# encoder.net
KiCad netlist of a schematic drawn in EAGLE
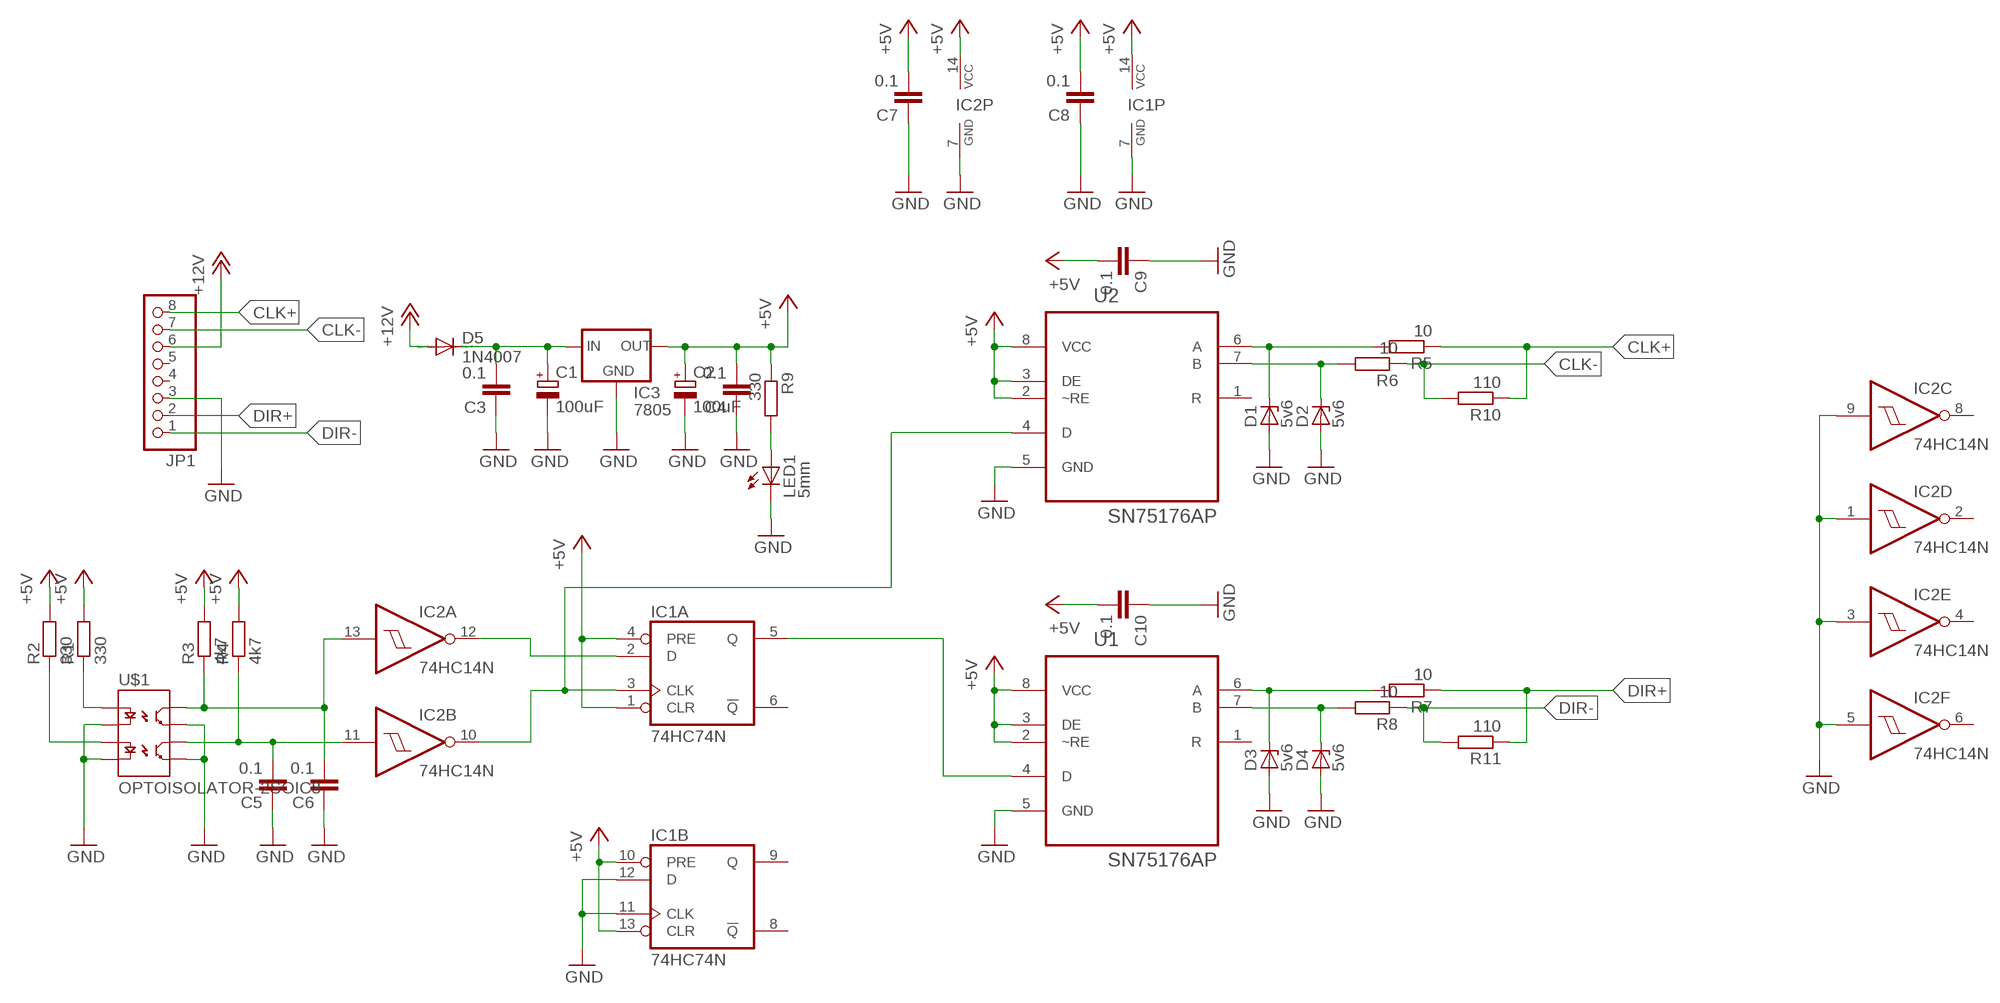
[diagram p0: schematic, sheet 1]

(export (version "E")
  (design (tool "Eeschema 10.0.6"))
  (components
    (comp (ref "C1")
      (value "100uF")
      (footprint "eagle-import:E3,5-8")
      (libsource (lib "eagle-import") (part "CPOL-EUE3.5-8"))
    )
    (comp (ref "C2")
      (value "100uF")
      (footprint "eagle-import:E3,5-8")
      (libsource (lib "eagle-import") (part "CPOL-EUE3.5-8"))
    )
    (comp (ref "C3")
      (value "0.1")
      (footprint "eagle-import:C050-025X075")
      (libsource (lib "eagle-import") (part "C-EU050-025X075"))
    )
    (comp (ref "C4")
      (value "0.1")
      (footprint "eagle-import:C050-025X075")
      (libsource (lib "eagle-import") (part "C-EU050-025X075"))
    )
    (comp (ref "C5")
      (value "0.1")
      (footprint "eagle-import:C050-025X075")
      (libsource (lib "eagle-import") (part "C-EU050-025X075"))
    )
    (comp (ref "C6")
      (value "0.1")
      (footprint "eagle-import:C050-025X075")
      (libsource (lib "eagle-import") (part "C-EU050-025X075"))
    )
    (comp (ref "C7")
      (value "0.1")
      (footprint "eagle-import:C050-025X075")
      (libsource (lib "eagle-import") (part "C-EU050-025X075"))
    )
    (comp (ref "C8")
      (value "0.1")
      (footprint "eagle-import:C050-025X075")
      (libsource (lib "eagle-import") (part "C-EU050-025X075"))
    )
    (comp (ref "C9")
      (value "0.1")
      (footprint "eagle-import:C050-025X075")
      (libsource (lib "eagle-import") (part "C-EU050-025X075"))
    )
    (comp (ref "C10")
      (value "0.1")
      (footprint "eagle-import:C050-025X075")
      (libsource (lib "eagle-import") (part "C-EU050-025X075"))
    )
    (comp (ref "D1")
      (value "5v6")
      (footprint "eagle-import:ZDIO-7.5")
      (libsource (lib "eagle-import") (part "ZENER-DIODEZD-7.5"))
    )
    (comp (ref "D2")
      (value "5v6")
      (footprint "eagle-import:ZDIO-7.5")
      (libsource (lib "eagle-import") (part "ZENER-DIODEZD-7.5"))
    )
    (comp (ref "D3")
      (value "5v6")
      (footprint "eagle-import:ZDIO-7.5")
      (libsource (lib "eagle-import") (part "ZENER-DIODEZD-7.5"))
    )
    (comp (ref "D4")
      (value "5v6")
      (footprint "eagle-import:ZDIO-7.5")
      (libsource (lib "eagle-import") (part "ZENER-DIODEZD-7.5"))
    )
    (comp (ref "D5")
      (value "1N4007")
      (footprint "eagle-import:DO41-7.6")
      (libsource (lib "eagle-import") (part "DIODE-DO41-7.6"))
    )
    (comp (ref "IC1")
      (value "74HC74N")
      (footprint "eagle-import:DIL14")
      (libsource (lib "eagle-import") (part "7474NAC"))
    )
    (comp (ref "IC2")
      (value "74HC14N")
      (footprint "eagle-import:DIL14")
      (libsource (lib "eagle-import") (part "7414NAC"))
    )
    (comp (ref "IC3")
      (value "7805")
      (footprint "eagle-import:78XXS")
      (libsource (lib "eagle-import") (part "78XXS"))
    )
    (comp (ref "JP1")
      (value "PINHD-1X8")
      (footprint "eagle-import:1X08")
      (libsource (lib "eagle-import") (part "PINHD-1X8"))
    )
    (comp (ref "LED1")
      (value "5mm")
      (footprint "eagle-import:LED5MM")
      (libsource (lib "eagle-import") (part "LED5MM"))
    )
    (comp (ref "R1")
      (value "330")
      (footprint "eagle-import:0204_7")
      (libsource (lib "eagle-import") (part "R-EU_0204/7"))
    )
    (comp (ref "R2")
      (value "330")
      (footprint "eagle-import:0204_7")
      (libsource (lib "eagle-import") (part "R-EU_0204/7"))
    )
    (comp (ref "R3")
      (value "4k7")
      (footprint "eagle-import:0204_7")
      (libsource (lib "eagle-import") (part "R-EU_0204/7"))
    )
    (comp (ref "R4")
      (value "4k7")
      (footprint "eagle-import:0204_7")
      (libsource (lib "eagle-import") (part "R-EU_0204/7"))
    )
    (comp (ref "R5")
      (value "10")
      (footprint "eagle-import:0204_7")
      (libsource (lib "eagle-import") (part "R-EU_0204/7"))
    )
    (comp (ref "R6")
      (value "10")
      (footprint "eagle-import:0204_7")
      (libsource (lib "eagle-import") (part "R-EU_0204/7"))
    )
    (comp (ref "R7")
      (value "10")
      (footprint "eagle-import:0204_7")
      (libsource (lib "eagle-import") (part "R-EU_0204/7"))
    )
    (comp (ref "R8")
      (value "10")
      (footprint "eagle-import:0204_7")
      (libsource (lib "eagle-import") (part "R-EU_0204/7"))
    )
    (comp (ref "R9")
      (value "330")
      (footprint "eagle-import:0204_7")
      (libsource (lib "eagle-import") (part "R-EU_0204/7"))
    )
    (comp (ref "R10")
      (value "110")
      (footprint "eagle-import:0204_7")
      (libsource (lib "eagle-import") (part "R-EU_0204/7"))
    )
    (comp (ref "R11")
      (value "110")
      (footprint "eagle-import:0204_7")
      (libsource (lib "eagle-import") (part "R-EU_0204/7"))
    )
    (comp (ref "U$1")
      (value "OPTOISOLATOR-2SOIC8")
      (footprint "eagle-import:SO08-2")
      (libsource (lib "eagle-import") (part "OPTOISOLATOR-2SOIC8"))
    )
    (comp (ref "U1")
      (value "SN75176AP")
      (footprint "eagle-import:DIP254P762X508-8")
      (libsource (lib "eagle-import") (part "SN75176AP"))
    )
    (comp (ref "U2")
      (value "SN75176AP")
      (footprint "eagle-import:DIP254P762X508-8")
      (libsource (lib "eagle-import") (part "SN75176AP"))
    )
  )
  (nets
    (net (code "1") (name "+5V") (class "Default")
      (node (ref "C10") (pin "2") (pinfunction "2_2") (pintype "passive"))
      (node (ref "C2") (pin "+") (pinfunction "+_+") (pintype "passive"))
      (node (ref "C4") (pin "2") (pinfunction "2_2") (pintype "passive"))
      (node (ref "C7") (pin "2") (pinfunction "2_2") (pintype "passive"))
      (node (ref "C8") (pin "2") (pinfunction "2_2") (pintype "passive"))
      (node (ref "C9") (pin "2") (pinfunction "2_2") (pintype "passive"))
      (node (ref "IC1") (pin "1") (pinfunction "CLR_1") (pintype "input"))
      (node (ref "IC1") (pin "10") (pinfunction "PRE_10") (pintype "input"))
      (node (ref "IC1") (pin "13") (pinfunction "CLR_13") (pintype "input"))
      (node (ref "IC1") (pin "14") (pinfunction "VCC_14") (pintype "power_in"))
      (node (ref "IC1") (pin "4") (pinfunction "PRE_4") (pintype "input"))
      (node (ref "IC2") (pin "14") (pinfunction "VCC_14") (pintype "power_in"))
      (node (ref "IC3") (pin "OUT") (pinfunction "OUT_OUT") (pintype "passive"))
      (node (ref "R1") (pin "2") (pinfunction "2_2") (pintype "passive"))
      (node (ref "R2") (pin "2") (pinfunction "2_2") (pintype "passive"))
      (node (ref "R3") (pin "2") (pinfunction "2_2") (pintype "passive"))
      (node (ref "R4") (pin "2") (pinfunction "2_2") (pintype "passive"))
      (node (ref "R9") (pin "1") (pinfunction "1_1") (pintype "passive"))
      (node (ref "U1") (pin "2") (pinfunction "~{RE}_2") (pintype "input"))
      (node (ref "U1") (pin "3") (pinfunction "DE_3") (pintype "input"))
      (node (ref "U1") (pin "8") (pinfunction "VCC_8") (pintype "power_in"))
      (node (ref "U2") (pin "2") (pinfunction "~{RE}_2") (pintype "input"))
      (node (ref "U2") (pin "3") (pinfunction "DE_3") (pintype "input"))
      (node (ref "U2") (pin "8") (pinfunction "VCC_8") (pintype "power_in"))
    )
    (net (code "2") (name "+12V") (class "Default")
      (node (ref "D5") (pin "A") (pinfunction "A_A") (pintype "passive"))
      (node (ref "JP1") (pin "6") (pinfunction "6_6") (pintype "passive"))
    )
    (net (code "3") (name "CLK+") (class "Default")
      (node (ref "JP1") (pin "8") (pinfunction "8_8") (pintype "passive"))
      (node (ref "R10") (pin "1") (pinfunction "1_1") (pintype "passive"))
      (node (ref "R5") (pin "1") (pinfunction "1_1") (pintype "passive"))
    )
    (net (code "4") (name "CLK-") (class "Default")
      (node (ref "JP1") (pin "7") (pinfunction "7_7") (pintype "passive"))
      (node (ref "R10") (pin "2") (pinfunction "2_2") (pintype "passive"))
      (node (ref "R6") (pin "1") (pinfunction "1_1") (pintype "passive"))
    )
    (net (code "5") (name "DIR+") (class "Default")
      (node (ref "JP1") (pin "2") (pinfunction "2_2") (pintype "passive"))
      (node (ref "R11") (pin "1") (pinfunction "1_1") (pintype "passive"))
      (node (ref "R7") (pin "1") (pinfunction "1_1") (pintype "passive"))
    )
    (net (code "6") (name "DIR-") (class "Default")
      (node (ref "JP1") (pin "1") (pinfunction "1_1") (pintype "passive"))
      (node (ref "R11") (pin "2") (pinfunction "2_2") (pintype "passive"))
      (node (ref "R8") (pin "1") (pinfunction "1_1") (pintype "passive"))
    )
    (net (code "7") (name "GND") (class "Default")
      (node (ref "C1") (pin "-") (pinfunction "-_-") (pintype "passive"))
      (node (ref "C10") (pin "1") (pinfunction "1_1") (pintype "passive"))
      (node (ref "C2") (pin "-") (pinfunction "-_-") (pintype "passive"))
      (node (ref "C3") (pin "1") (pinfunction "1_1") (pintype "passive"))
      (node (ref "C4") (pin "1") (pinfunction "1_1") (pintype "passive"))
      (node (ref "C5") (pin "1") (pinfunction "1_1") (pintype "passive"))
      (node (ref "C6") (pin "1") (pinfunction "1_1") (pintype "passive"))
      (node (ref "C7") (pin "1") (pinfunction "1_1") (pintype "passive"))
      (node (ref "C8") (pin "1") (pinfunction "1_1") (pintype "passive"))
      (node (ref "C9") (pin "1") (pinfunction "1_1") (pintype "passive"))
      (node (ref "D1") (pin "A") (pinfunction "A_A") (pintype "passive"))
      (node (ref "D2") (pin "A") (pinfunction "A_A") (pintype "passive"))
      (node (ref "D3") (pin "A") (pinfunction "A_A") (pintype "passive"))
      (node (ref "D4") (pin "A") (pinfunction "A_A") (pintype "passive"))
      (node (ref "IC1") (pin "11") (pinfunction "CLK_11") (pintype "input"))
      (node (ref "IC1") (pin "12") (pinfunction "D_12") (pintype "input"))
      (node (ref "IC1") (pin "7") (pinfunction "GND_7") (pintype "power_in"))
      (node (ref "IC2") (pin "1") (pinfunction "I_1") (pintype "input"))
      (node (ref "IC2") (pin "3") (pinfunction "I_3") (pintype "input"))
      (node (ref "IC2") (pin "5") (pinfunction "I_5") (pintype "input"))
      (node (ref "IC2") (pin "7") (pinfunction "GND_7") (pintype "power_in"))
      (node (ref "IC2") (pin "9") (pinfunction "I_9") (pintype "input"))
      (node (ref "IC3") (pin "GND") (pinfunction "GND_GND") (pintype "input"))
      (node (ref "JP1") (pin "3") (pinfunction "3_3") (pintype "passive"))
      (node (ref "LED1") (pin "K") (pinfunction "C_K") (pintype "passive"))
      (node (ref "U$1") (pin "2") (pinfunction "C1_2") (pintype "bidirectional"))
      (node (ref "U$1") (pin "4") (pinfunction "C2_4") (pintype "bidirectional"))
      (node (ref "U$1") (pin "5") (pinfunction "EM2_5") (pintype "bidirectional"))
      (node (ref "U$1") (pin "7") (pinfunction "EM1_7") (pintype "bidirectional"))
      (node (ref "U1") (pin "5") (pinfunction "GND_5") (pintype "passive"))
      (node (ref "U2") (pin "5") (pinfunction "GND_5") (pintype "passive"))
    )
    (net (code "8") (name "Net-(C1-Pad+)") (class "Default")
      (node (ref "C1") (pin "+") (pinfunction "+_+") (pintype "passive"))
      (node (ref "C3") (pin "2") (pinfunction "2_2") (pintype "passive"))
      (node (ref "D5") (pin "C") (pinfunction "C_C") (pintype "passive"))
      (node (ref "IC3") (pin "IN") (pinfunction "IN_IN") (pintype "input"))
    )
    (net (code "9") (name "Net-(IC1A-CLK)") (class "Default")
      (node (ref "IC1") (pin "3") (pinfunction "CLK_3") (pintype "input"))
      (node (ref "IC2") (pin "10") (pinfunction "O_10") (pintype "output"))
      (node (ref "U2") (pin "4") (pinfunction "D_4") (pintype "input"))
    )
    (net (code "10") (name "Net-(IC1A-D)") (class "Default")
      (node (ref "IC1") (pin "2") (pinfunction "D_2") (pintype "input"))
      (node (ref "IC2") (pin "12") (pinfunction "O_12") (pintype "output"))
    )
    (net (code "11") (name "Net-(IC1A-Q)") (class "Default")
      (node (ref "IC1") (pin "5") (pinfunction "Q_5") (pintype "output"))
      (node (ref "U1") (pin "4") (pinfunction "D_4") (pintype "input"))
    )
    (net (code "12") (name "Net-(IC2A-I)") (class "Default")
      (node (ref "C6") (pin "2") (pinfunction "2_2") (pintype "passive"))
      (node (ref "IC2") (pin "13") (pinfunction "I_13") (pintype "input"))
      (node (ref "R3") (pin "1") (pinfunction "1_1") (pintype "passive"))
      (node (ref "U$1") (pin "8") (pinfunction "CL1_8") (pintype "bidirectional"))
    )
    (net (code "13") (name "Net-(IC2B-I)") (class "Default")
      (node (ref "C5") (pin "2") (pinfunction "2_2") (pintype "passive"))
      (node (ref "IC2") (pin "11") (pinfunction "I_11") (pintype "input"))
      (node (ref "R4") (pin "1") (pinfunction "1_1") (pintype "passive"))
      (node (ref "U$1") (pin "6") (pinfunction "CL2_6") (pintype "bidirectional"))
    )
    (net (code "14") (name "Net-(LED1-PadA)") (class "Default")
      (node (ref "LED1") (pin "A") (pinfunction "A_A") (pintype "passive"))
      (node (ref "R9") (pin "2") (pinfunction "2_2") (pintype "passive"))
    )
    (net (code "15") (name "Net-(U$1-A1)") (class "Default")
      (node (ref "R1") (pin "1") (pinfunction "1_1") (pintype "passive"))
      (node (ref "U$1") (pin "1") (pinfunction "A1_1") (pintype "bidirectional"))
    )
    (net (code "16") (name "Net-(U$1-A2)") (class "Default")
      (node (ref "R2") (pin "1") (pinfunction "1_1") (pintype "passive"))
      (node (ref "U$1") (pin "3") (pinfunction "A2_3") (pintype "bidirectional"))
    )
    (net (code "17") (name "Net-(U1-A)") (class "Default")
      (node (ref "D3") (pin "C") (pinfunction "C_C") (pintype "passive"))
      (node (ref "R7") (pin "2") (pinfunction "2_2") (pintype "passive"))
      (node (ref "U1") (pin "6") (pinfunction "A_6") (pintype "bidirectional"))
    )
    (net (code "18") (name "Net-(U1-B)") (class "Default")
      (node (ref "D4") (pin "C") (pinfunction "C_C") (pintype "passive"))
      (node (ref "R8") (pin "2") (pinfunction "2_2") (pintype "passive"))
      (node (ref "U1") (pin "7") (pinfunction "B_7") (pintype "bidirectional"))
    )
    (net (code "19") (name "Net-(U2-A)") (class "Default")
      (node (ref "D1") (pin "C") (pinfunction "C_C") (pintype "passive"))
      (node (ref "R5") (pin "2") (pinfunction "2_2") (pintype "passive"))
      (node (ref "U2") (pin "6") (pinfunction "A_6") (pintype "bidirectional"))
    )
    (net (code "20") (name "Net-(U2-B)") (class "Default")
      (node (ref "D2") (pin "C") (pinfunction "C_C") (pintype "passive"))
      (node (ref "R6") (pin "2") (pinfunction "2_2") (pintype "passive"))
      (node (ref "U2") (pin "7") (pinfunction "B_7") (pintype "bidirectional"))
    )
    (net (code "21") (name "unconnected-(IC1A-~{Q}-Pad6)") (class "Default")
      (node (ref "IC1") (pin "6") (pinfunction "~{Q}_6") (pintype "output"))
    )
    (net (code "22") (name "unconnected-(IC1B-Q-Pad9)") (class "Default")
      (node (ref "IC1") (pin "9") (pinfunction "Q_9") (pintype "output"))
    )
    (net (code "23") (name "unconnected-(IC1B-~{Q}-Pad8)") (class "Default")
      (node (ref "IC1") (pin "8") (pinfunction "~{Q}_8") (pintype "output"))
    )
    (net (code "24") (name "unconnected-(IC2C-O-Pad8)") (class "Default")
      (node (ref "IC2") (pin "8") (pinfunction "O_8") (pintype "output"))
    )
    (net (code "25") (name "unconnected-(IC2D-O-Pad2)") (class "Default")
      (node (ref "IC2") (pin "2") (pinfunction "O_2") (pintype "output"))
    )
    (net (code "26") (name "unconnected-(IC2E-O-Pad4)") (class "Default")
      (node (ref "IC2") (pin "4") (pinfunction "O_4") (pintype "output"))
    )
    (net (code "27") (name "unconnected-(IC2F-O-Pad6)") (class "Default")
      (node (ref "IC2") (pin "6") (pinfunction "O_6") (pintype "output"))
    )
    (net (code "28") (name "unconnected-(JP1-Pad4)") (class "Default")
      (node (ref "JP1") (pin "4") (pinfunction "4_4") (pintype "passive"))
    )
    (net (code "29") (name "unconnected-(JP1-Pad5)") (class "Default")
      (node (ref "JP1") (pin "5") (pinfunction "5_5") (pintype "passive"))
    )
    (net (code "30") (name "unconnected-(U1-R-Pad1)") (class "Default")
      (node (ref "U1") (pin "1") (pinfunction "R_1") (pintype "output"))
    )
    (net (code "31") (name "unconnected-(U2-R-Pad1)") (class "Default")
      (node (ref "U2") (pin "1") (pinfunction "R_1") (pintype "output"))
    )
  )
)
